# Test2.net
KiCad netlist of a schematic drawn in EAGLE
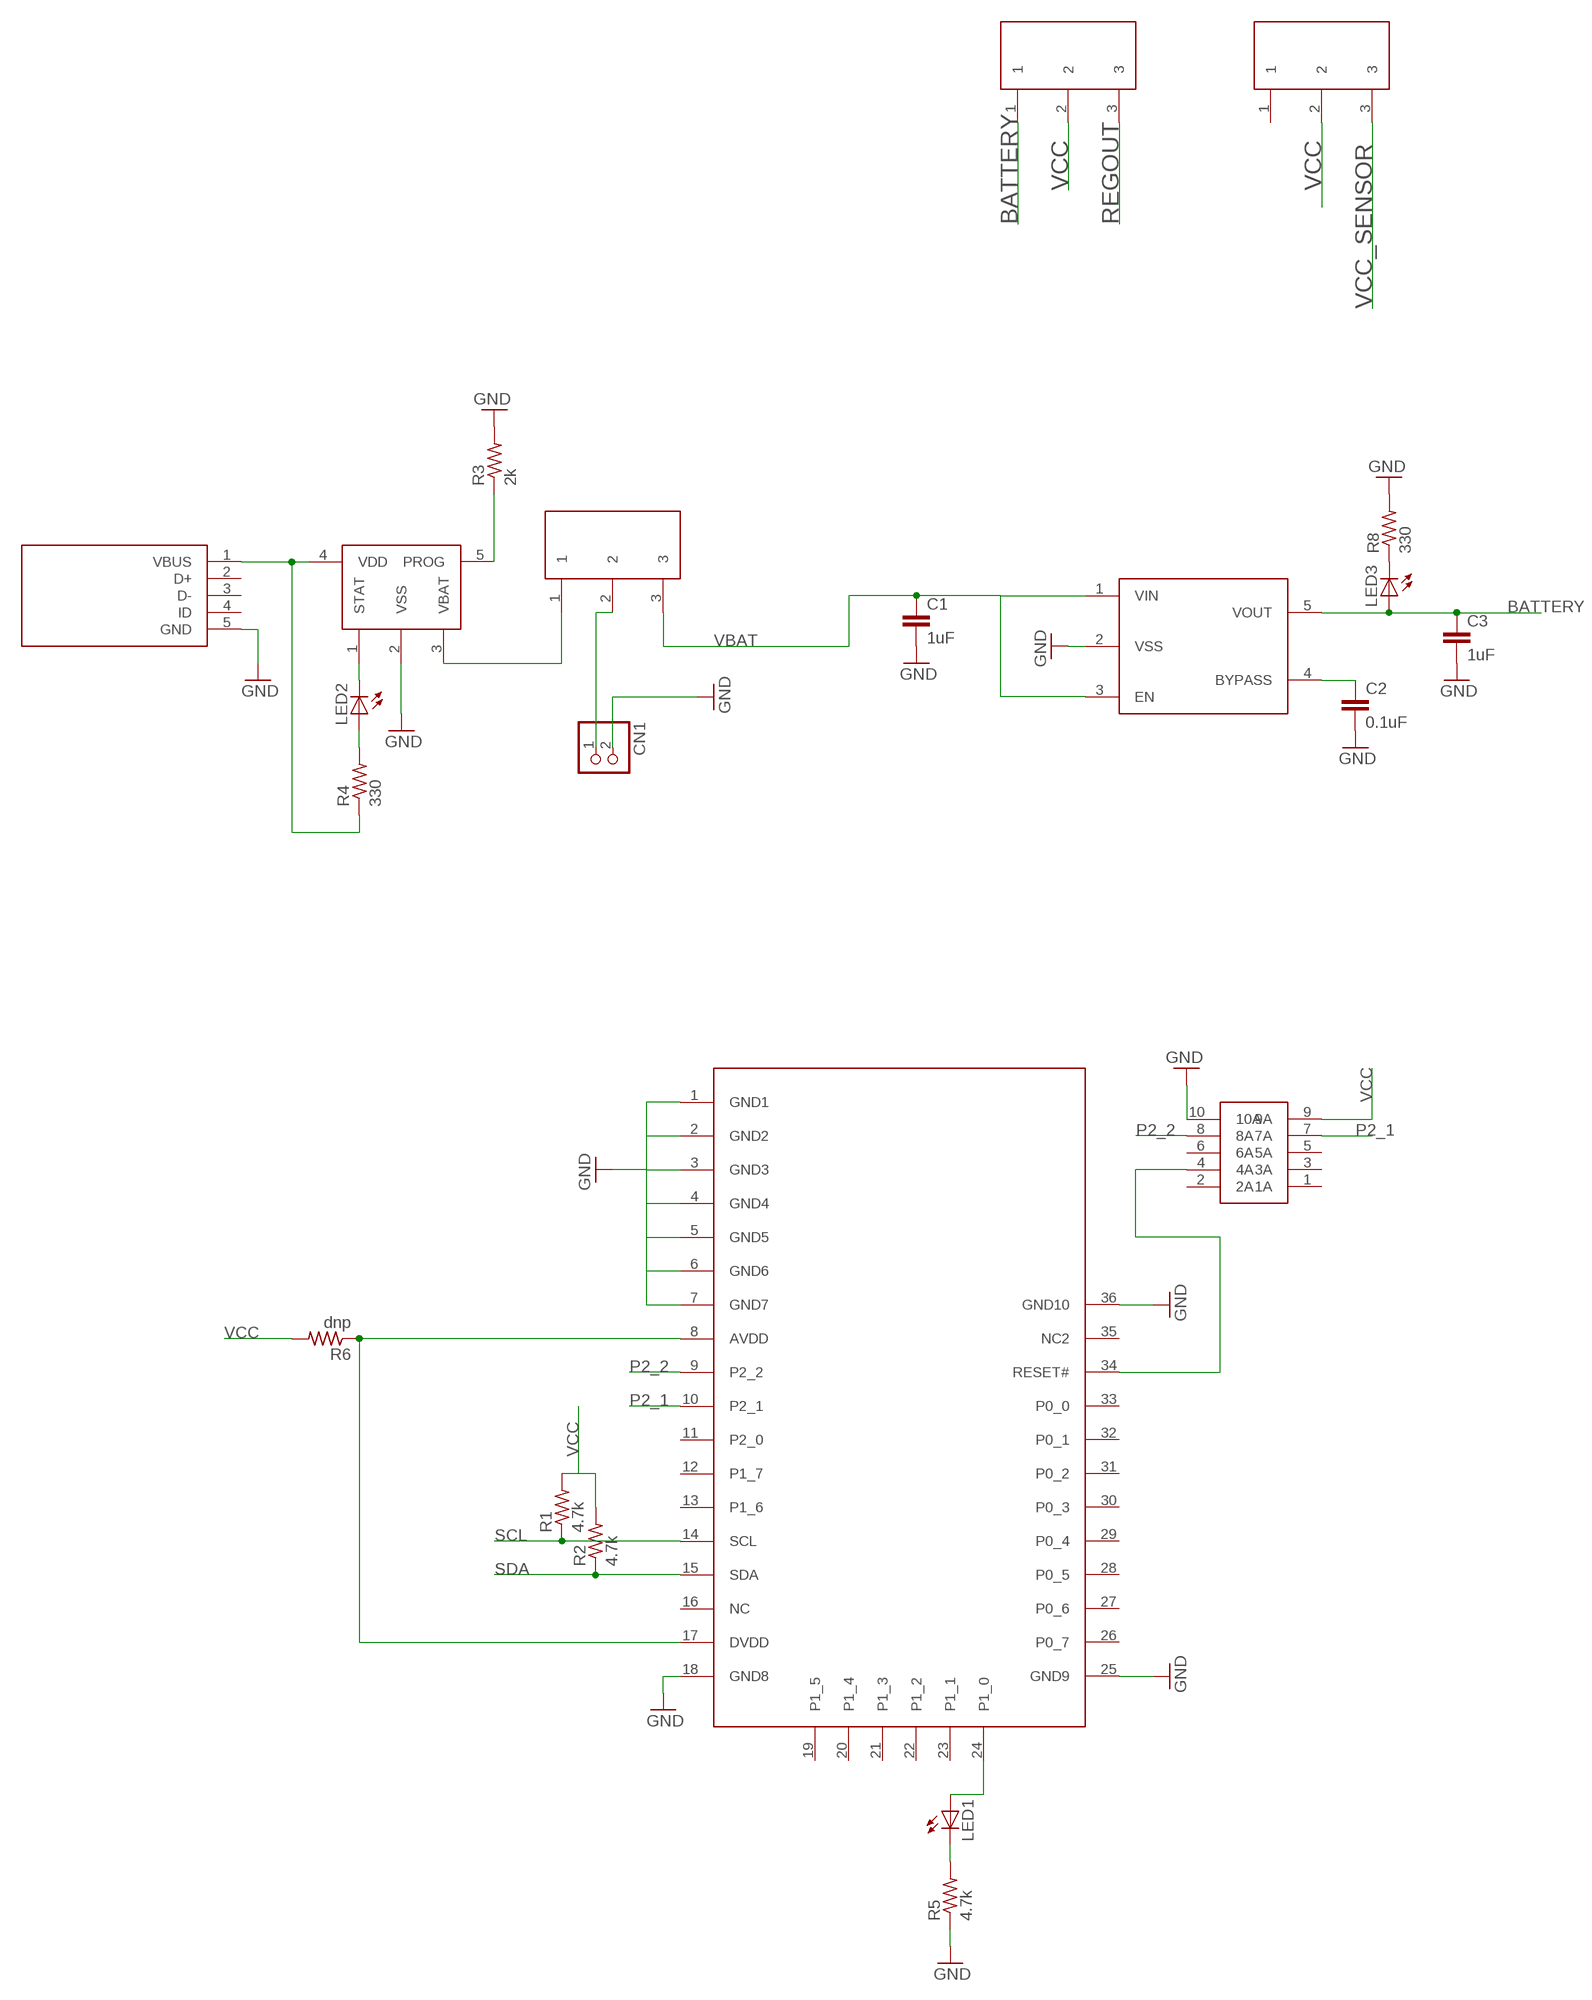
[diagram p0: schematic, sheet 1, part 1 of 2]
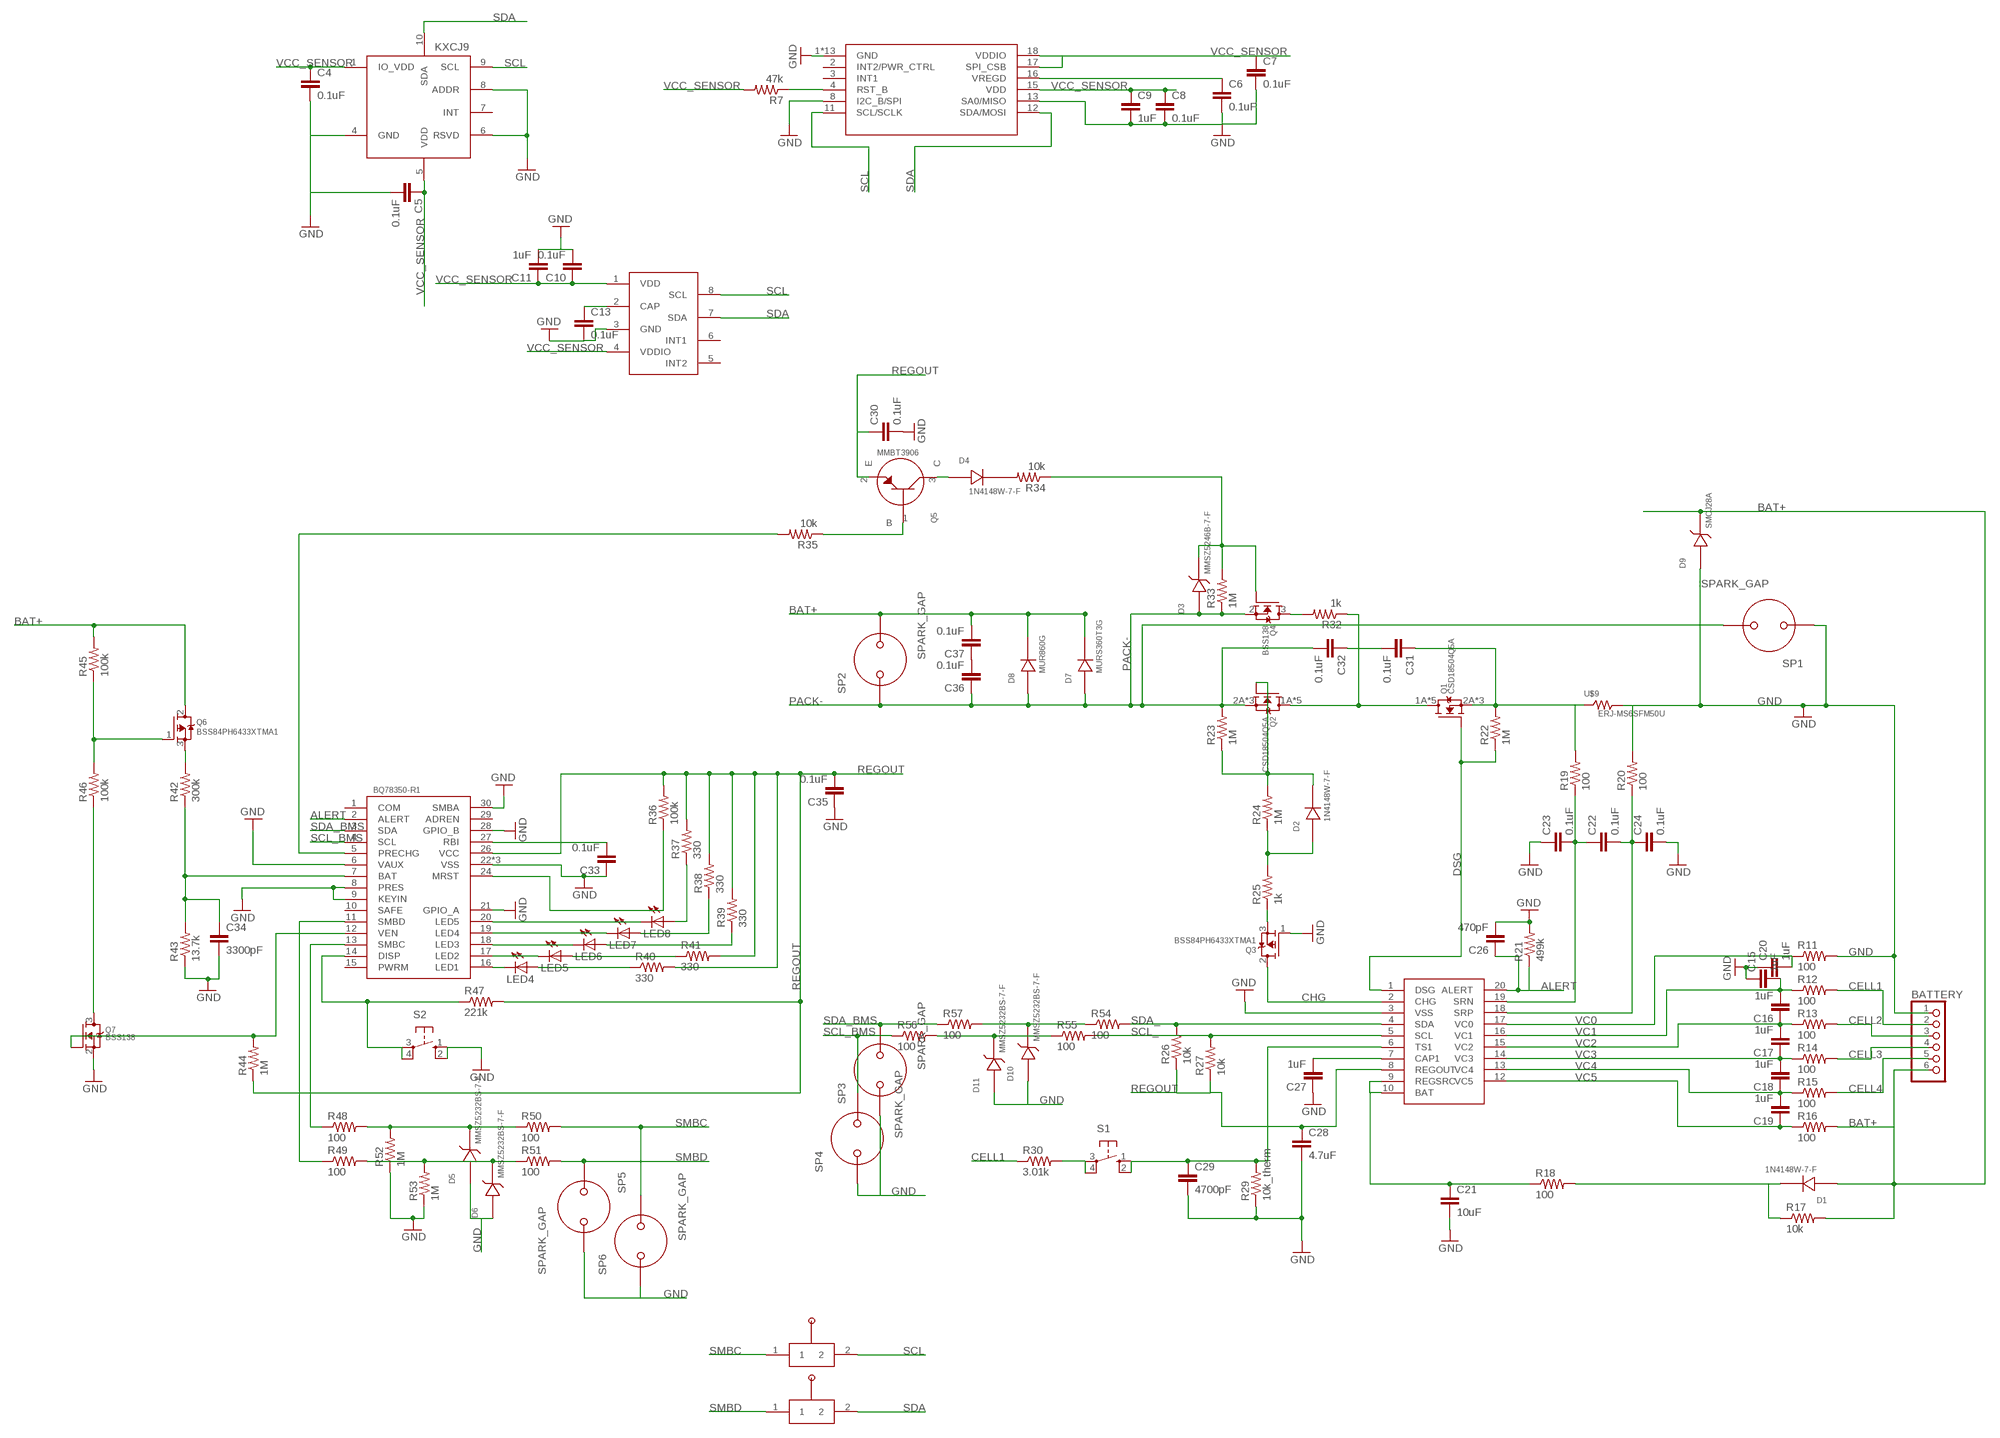
[diagram p1: schematic, sheet 1, part 2 of 2]

(export (version "E")
  (design (tool "Eeschema 10.0.6"))
  (components
    (comp (ref "BATTERY")
      (value "PINHD-1X6")
      (footprint "eagle-import:1X06")
      (libsource (lib "eagle-import") (part "PINHD-1X6"))
    )
    (comp (ref "C1")
      (value "1uF")
      (footprint "eagle-import:C0402")
      (libsource (lib "eagle-import") (part "C-EUC0402"))
    )
    (comp (ref "C2")
      (value "0.1uF")
      (footprint "eagle-import:C0402")
      (libsource (lib "eagle-import") (part "C-EUC0402"))
    )
    (comp (ref "C3")
      (value "1uF")
      (footprint "eagle-import:C0402")
      (libsource (lib "eagle-import") (part "C-EUC0402"))
    )
    (comp (ref "C4")
      (value "0.1uF")
      (footprint "eagle-import:C0402")
      (libsource (lib "eagle-import") (part "C-EUC0402"))
    )
    (comp (ref "C5")
      (value "0.1uF")
      (footprint "eagle-import:C0402")
      (libsource (lib "eagle-import") (part "C-EUC0402"))
    )
    (comp (ref "C6")
      (value "0.1uF")
      (footprint "eagle-import:C0402")
      (libsource (lib "eagle-import") (part "C-EUC0402"))
    )
    (comp (ref "C7")
      (value "0.1uF")
      (footprint "eagle-import:C0402")
      (libsource (lib "eagle-import") (part "C-EUC0402"))
    )
    (comp (ref "C8")
      (value "0.1uF")
      (footprint "eagle-import:C0402")
      (libsource (lib "eagle-import") (part "C-EUC0402"))
    )
    (comp (ref "C9")
      (value "1uF")
      (footprint "eagle-import:C0402")
      (libsource (lib "eagle-import") (part "C-EUC0402"))
    )
    (comp (ref "C10")
      (value "0.1uF")
      (footprint "eagle-import:C0402")
      (libsource (lib "eagle-import") (part "C-EUC0402"))
    )
    (comp (ref "C11")
      (value "1uF")
      (footprint "eagle-import:C0402")
      (libsource (lib "eagle-import") (part "C-EUC0402"))
    )
    (comp (ref "C13")
      (value "0.1uF")
      (footprint "eagle-import:C0402")
      (libsource (lib "eagle-import") (part "C-EUC0402"))
    )
    (comp (ref "C15")
      (value "1uF")
      (footprint "eagle-import:C0805")
      (libsource (lib "eagle-import") (part "C-EUC0805"))
    )
    (comp (ref "C16")
      (value "1uF")
      (footprint "eagle-import:C0805")
      (libsource (lib "eagle-import") (part "C-EUC0805"))
    )
    (comp (ref "C17")
      (value "1uF")
      (footprint "eagle-import:C0805")
      (libsource (lib "eagle-import") (part "C-EUC0805"))
    )
    (comp (ref "C18")
      (value "1uF")
      (footprint "eagle-import:C0805")
      (libsource (lib "eagle-import") (part "C-EUC0805"))
    )
    (comp (ref "C19")
      (value "1uF")
      (footprint "eagle-import:C0805")
      (libsource (lib "eagle-import") (part "C-EUC0805"))
    )
    (comp (ref "C20")
      (value "1uF")
      (footprint "eagle-import:C0805")
      (libsource (lib "eagle-import") (part "C-EUC0805"))
    )
    (comp (ref "C21")
      (value "10uF")
      (footprint "eagle-import:C1206")
      (libsource (lib "eagle-import") (part "C-EUC1206"))
    )
    (comp (ref "C22")
      (value "0.1uF")
      (footprint "eagle-import:C0805")
      (libsource (lib "eagle-import") (part "C-EUC0805"))
    )
    (comp (ref "C23")
      (value "0.1uF")
      (footprint "eagle-import:C0805")
      (libsource (lib "eagle-import") (part "C-EUC0805"))
    )
    (comp (ref "C24")
      (value "0.1uF")
      (footprint "eagle-import:C0805")
      (libsource (lib "eagle-import") (part "C-EUC0805"))
    )
    (comp (ref "C26")
      (value "470pF")
      (footprint "eagle-import:C0805")
      (libsource (lib "eagle-import") (part "C-EUC0805"))
    )
    (comp (ref "C27")
      (value "1uF")
      (footprint "eagle-import:C0805")
      (libsource (lib "eagle-import") (part "C-EUC0805"))
    )
    (comp (ref "C28")
      (value "4.7uF")
      (footprint "eagle-import:C0805")
      (libsource (lib "eagle-import") (part "C-EUC0805"))
    )
    (comp (ref "C29")
      (value "4700pF")
      (footprint "eagle-import:C0402")
      (libsource (lib "eagle-import") (part "C-EUC0402"))
    )
    (comp (ref "C30")
      (value "0.1uF")
      (footprint "eagle-import:C0805")
      (libsource (lib "eagle-import") (part "C-EUC0805"))
    )
    (comp (ref "C31")
      (value "0.1uF")
      (footprint "eagle-import:C0805")
      (libsource (lib "eagle-import") (part "C-EUC0805"))
    )
    (comp (ref "C32")
      (value "0.1uF")
      (footprint "eagle-import:C0805")
      (libsource (lib "eagle-import") (part "C-EUC0805"))
    )
    (comp (ref "C33")
      (value "0.1uF")
      (footprint "eagle-import:C0805")
      (libsource (lib "eagle-import") (part "C-EUC0805"))
    )
    (comp (ref "C34")
      (value "3300pF")
      (footprint "eagle-import:C0402")
      (libsource (lib "eagle-import") (part "C-EUC0402"))
    )
    (comp (ref "C35")
      (value "0.1uF")
      (footprint "eagle-import:C0805")
      (libsource (lib "eagle-import") (part "C-EUC0805"))
    )
    (comp (ref "C36")
      (value "0.1uF")
      (footprint "eagle-import:C0805")
      (libsource (lib "eagle-import") (part "C-EUC0805"))
    )
    (comp (ref "C37")
      (value "0.1uF")
      (footprint "eagle-import:C0805")
      (libsource (lib "eagle-import") (part "C-EUC0805"))
    )
    (comp (ref "CN1")
      (value "JST_2PIN-SMT-RA")
      (footprint "eagle-import:JST-PH-2-SMT-RA")
      (libsource (lib "eagle-import") (part "JST_2PIN-SMT-RA"))
    )
    (comp (ref "D1")
      (value "1N4148W-7-F")
      (footprint "eagle-import:SOD-123")
      (libsource (lib "eagle-import") (part "1N4148W-7-F"))
    )
    (comp (ref "D2")
      (value "1N4148W-7-F")
      (footprint "eagle-import:SOD-123")
      (libsource (lib "eagle-import") (part "1N4148W-7-F"))
    )
    (comp (ref "D3")
      (value "MMSZ5246B-7-F")
      (footprint "eagle-import:SOD-123")
      (libsource (lib "eagle-import") (part "MMSZ5246B-7-F"))
    )
    (comp (ref "D4")
      (value "1N4148W-7-F")
      (footprint "eagle-import:SOD-123")
      (libsource (lib "eagle-import") (part "1N4148W-7-F"))
    )
    (comp (ref "D5")
      (value "MMSZ5232BS-7-F")
      (footprint "eagle-import:SOD-323F")
      (libsource (lib "eagle-import") (part "MMSZ5232BS-7-F"))
    )
    (comp (ref "D6")
      (value "MMSZ5232BS-7-F")
      (footprint "eagle-import:SOD-323F")
      (libsource (lib "eagle-import") (part "MMSZ5232BS-7-F"))
    )
    (comp (ref "D7")
      (value "MURS360T3G")
      (footprint "eagle-import:SMC(DO-214AB)")
      (libsource (lib "eagle-import") (part "MURS360T3G"))
    )
    (comp (ref "D8")
      (value "MUR860G")
      (footprint "eagle-import:TO-220(2RA)")
      (libsource (lib "eagle-import") (part "MUR860G"))
    )
    (comp (ref "D9")
      (value "SMCJ28A")
      (footprint "eagle-import:SMC(DO-214AB)")
      (libsource (lib "eagle-import") (part "SMCJ28A"))
    )
    (comp (ref "D10")
      (value "MMSZ5232BS-7-F")
      (footprint "eagle-import:SOD-323F")
      (libsource (lib "eagle-import") (part "MMSZ5232BS-7-F"))
    )
    (comp (ref "D11")
      (value "MMSZ5232BS-7-F")
      (footprint "eagle-import:SOD-323F")
      (libsource (lib "eagle-import") (part "MMSZ5232BS-7-F"))
    )
    (comp (ref "LED1")
      (value "LEDCHIP-LED0805")
      (footprint "eagle-import:CHIP-LED0805")
      (libsource (lib "eagle-import") (part "LEDCHIP-LED0805"))
    )
    (comp (ref "LED2")
      (value "LEDCHIP-LED0805")
      (footprint "eagle-import:CHIP-LED0805")
      (libsource (lib "eagle-import") (part "LEDCHIP-LED0805"))
    )
    (comp (ref "LED3")
      (value "LEDCHIP-LED0805")
      (footprint "eagle-import:CHIP-LED0805")
      (libsource (lib "eagle-import") (part "LEDCHIP-LED0805"))
    )
    (comp (ref "LED4")
      (value "LEDCHIPLED_0805")
      (footprint "eagle-import:CHIPLED_0805")
      (libsource (lib "eagle-import") (part "LEDCHIPLED_0805"))
    )
    (comp (ref "LED5")
      (value "LEDCHIPLED_0805")
      (footprint "eagle-import:CHIPLED_0805")
      (libsource (lib "eagle-import") (part "LEDCHIPLED_0805"))
    )
    (comp (ref "LED6")
      (value "LEDCHIPLED_0805")
      (footprint "eagle-import:CHIPLED_0805")
      (libsource (lib "eagle-import") (part "LEDCHIPLED_0805"))
    )
    (comp (ref "LED7")
      (value "LEDCHIPLED_0805")
      (footprint "eagle-import:CHIPLED_0805")
      (libsource (lib "eagle-import") (part "LEDCHIPLED_0805"))
    )
    (comp (ref "LED8")
      (value "LEDCHIPLED_0805")
      (footprint "eagle-import:CHIPLED_0805")
      (libsource (lib "eagle-import") (part "LEDCHIPLED_0805"))
    )
    (comp (ref "Q1")
      (value "CSD18504Q5A")
      (footprint "eagle-import:Q5A")
      (libsource (lib "eagle-import") (part "CSD18504Q5A"))
    )
    (comp (ref "Q2")
      (value "CSD18504Q5A")
      (footprint "eagle-import:Q5A")
      (libsource (lib "eagle-import") (part "CSD18504Q5A"))
    )
    (comp (ref "Q3")
      (value "BSS84PH6433XTMA1")
      (footprint "eagle-import:SOT23-3")
      (libsource (lib "eagle-import") (part "BSS84PH6433XTMA1"))
    )
    (comp (ref "Q4")
      (value "BSS138")
      (footprint "eagle-import:SOT23-3")
      (libsource (lib "eagle-import") (part "BSS138"))
    )
    (comp (ref "Q5")
      (value "MMBT3906")
      (footprint "eagle-import:SOT23-3")
      (libsource (lib "eagle-import") (part "MMBT3906"))
    )
    (comp (ref "Q6")
      (value "BSS84PH6433XTMA1")
      (footprint "eagle-import:SOT23-3")
      (libsource (lib "eagle-import") (part "BSS84PH6433XTMA1"))
    )
    (comp (ref "Q7")
      (value "BSS138")
      (footprint "eagle-import:SOT23-3")
      (libsource (lib "eagle-import") (part "BSS138"))
    )
    (comp (ref "R1")
      (value "4.7k")
      (footprint "eagle-import:R0402")
      (libsource (lib "eagle-import") (part "R-US_R0402"))
    )
    (comp (ref "R2")
      (value "4.7k")
      (footprint "eagle-import:R0402")
      (libsource (lib "eagle-import") (part "R-US_R0402"))
    )
    (comp (ref "R3")
      (value "2k")
      (footprint "eagle-import:R0402")
      (libsource (lib "eagle-import") (part "R-US_R0402"))
    )
    (comp (ref "R4")
      (value "330")
      (footprint "eagle-import:R0402")
      (libsource (lib "eagle-import") (part "R-US_R0402"))
    )
    (comp (ref "R5")
      (value "4.7k")
      (footprint "eagle-import:R0402")
      (libsource (lib "eagle-import") (part "R-US_R0402"))
    )
    (comp (ref "R6")
      (value "dnp")
      (footprint "eagle-import:R0402")
      (libsource (lib "eagle-import") (part "R-US_R0402"))
    )
    (comp (ref "R7")
      (value "47k")
      (footprint "eagle-import:R0402")
      (libsource (lib "eagle-import") (part "R-US_R0402"))
    )
    (comp (ref "R8")
      (value "330")
      (footprint "eagle-import:R0402")
      (libsource (lib "eagle-import") (part "R-US_R0402"))
    )
    (comp (ref "R11")
      (value "100")
      (footprint "eagle-import:R1206")
      (libsource (lib "eagle-import") (part "R-US_R1206"))
    )
    (comp (ref "R12")
      (value "100")
      (footprint "eagle-import:R1206")
      (libsource (lib "eagle-import") (part "R-US_R1206"))
    )
    (comp (ref "R13")
      (value "100")
      (footprint "eagle-import:R1206")
      (libsource (lib "eagle-import") (part "R-US_R1206"))
    )
    (comp (ref "R14")
      (value "100")
      (footprint "eagle-import:R1206")
      (libsource (lib "eagle-import") (part "R-US_R1206"))
    )
    (comp (ref "R15")
      (value "100")
      (footprint "eagle-import:R1206")
      (libsource (lib "eagle-import") (part "R-US_R1206"))
    )
    (comp (ref "R16")
      (value "100")
      (footprint "eagle-import:R1206")
      (libsource (lib "eagle-import") (part "R-US_R1206"))
    )
    (comp (ref "R17")
      (value "10k")
      (footprint "eagle-import:R0805")
      (libsource (lib "eagle-import") (part "R-US_R0805"))
    )
    (comp (ref "R18")
      (value "100")
      (footprint "eagle-import:R0805")
      (libsource (lib "eagle-import") (part "R-US_R0805"))
    )
    (comp (ref "R19")
      (value "100")
      (footprint "eagle-import:R0805")
      (libsource (lib "eagle-import") (part "R-US_R0805"))
    )
    (comp (ref "R20")
      (value "100")
      (footprint "eagle-import:R0805")
      (libsource (lib "eagle-import") (part "R-US_R0805"))
    )
    (comp (ref "R21")
      (value "499k")
      (footprint "eagle-import:R0805")
      (libsource (lib "eagle-import") (part "R-US_R0805"))
    )
    (comp (ref "R22")
      (value "1M")
      (footprint "eagle-import:R1206")
      (libsource (lib "eagle-import") (part "R-US_R1206"))
    )
    (comp (ref "R23")
      (value "1M")
      (footprint "eagle-import:R1206")
      (libsource (lib "eagle-import") (part "R-US_R1206"))
    )
    (comp (ref "R24")
      (value "1M")
      (footprint "eagle-import:R1206")
      (libsource (lib "eagle-import") (part "R-US_R1206"))
    )
    (comp (ref "R25")
      (value "1k")
      (footprint "eagle-import:R0805")
      (libsource (lib "eagle-import") (part "R-US_R0805"))
    )
    (comp (ref "R26")
      (value "10k")
      (footprint "eagle-import:R0805")
      (libsource (lib "eagle-import") (part "R-US_R0805"))
    )
    (comp (ref "R27")
      (value "10k")
      (footprint "eagle-import:R0805")
      (libsource (lib "eagle-import") (part "R-US_R0805"))
    )
    (comp (ref "R29")
      (value "10k_therm")
      (footprint "eagle-import:R0402")
      (libsource (lib "eagle-import") (part "R-US_R0402"))
    )
    (comp (ref "R30")
      (value "3.01k")
      (footprint "eagle-import:R0805")
      (libsource (lib "eagle-import") (part "R-US_R0805"))
    )
    (comp (ref "R32")
      (value "1k")
      (footprint "eagle-import:R2512")
      (libsource (lib "eagle-import") (part "R-US_R2512"))
    )
    (comp (ref "R33")
      (value "1M")
      (footprint "eagle-import:R1206")
      (libsource (lib "eagle-import") (part "R-US_R1206"))
    )
    (comp (ref "R34")
      (value "10k")
      (footprint "eagle-import:R0805")
      (libsource (lib "eagle-import") (part "R-US_R0805"))
    )
    (comp (ref "R35")
      (value "10k")
      (footprint "eagle-import:R0805")
      (libsource (lib "eagle-import") (part "R-US_R0805"))
    )
    (comp (ref "R36")
      (value "100k")
      (footprint "eagle-import:R0805")
      (libsource (lib "eagle-import") (part "R-US_R0805"))
    )
    (comp (ref "R37")
      (value "330")
      (footprint "eagle-import:R0402")
      (libsource (lib "eagle-import") (part "R-US_R0402"))
    )
    (comp (ref "R38")
      (value "330")
      (footprint "eagle-import:R0402")
      (libsource (lib "eagle-import") (part "R-US_R0402"))
    )
    (comp (ref "R39")
      (value "330")
      (footprint "eagle-import:R0402")
      (libsource (lib "eagle-import") (part "R-US_R0402"))
    )
    (comp (ref "R40")
      (value "330")
      (footprint "eagle-import:R0402")
      (libsource (lib "eagle-import") (part "R-US_R0402"))
    )
    (comp (ref "R41")
      (value "330")
      (footprint "eagle-import:R0402")
      (libsource (lib "eagle-import") (part "R-US_R0402"))
    )
    (comp (ref "R42")
      (value "300k")
      (footprint "eagle-import:R0805")
      (libsource (lib "eagle-import") (part "R-US_R0805"))
    )
    (comp (ref "R43")
      (value "13.7k")
      (footprint "eagle-import:R0805")
      (libsource (lib "eagle-import") (part "R-US_R0805"))
    )
    (comp (ref "R44")
      (value "1M")
      (footprint "eagle-import:R1206")
      (libsource (lib "eagle-import") (part "R-US_R1206"))
    )
    (comp (ref "R45")
      (value "100k")
      (footprint "eagle-import:R0805")
      (libsource (lib "eagle-import") (part "R-US_R0805"))
    )
    (comp (ref "R46")
      (value "100k")
      (footprint "eagle-import:R0805")
      (libsource (lib "eagle-import") (part "R-US_R0805"))
    )
    (comp (ref "R47")
      (value "221k")
      (footprint "eagle-import:R0805")
      (libsource (lib "eagle-import") (part "R-US_R0805"))
    )
    (comp (ref "R48")
      (value "100")
      (footprint "eagle-import:R0805")
      (libsource (lib "eagle-import") (part "R-US_R0805"))
    )
    (comp (ref "R49")
      (value "100")
      (footprint "eagle-import:R0805")
      (libsource (lib "eagle-import") (part "R-US_R0805"))
    )
    (comp (ref "R50")
      (value "100")
      (footprint "eagle-import:R0805")
      (libsource (lib "eagle-import") (part "R-US_R0805"))
    )
    (comp (ref "R51")
      (value "100")
      (footprint "eagle-import:R0805")
      (libsource (lib "eagle-import") (part "R-US_R0805"))
    )
    (comp (ref "R52")
      (value "1M")
      (footprint "eagle-import:R1206")
      (libsource (lib "eagle-import") (part "R-US_R1206"))
    )
    (comp (ref "R53")
      (value "1M")
      (footprint "eagle-import:R1206")
      (libsource (lib "eagle-import") (part "R-US_R1206"))
    )
    (comp (ref "R54")
      (value "100")
      (footprint "eagle-import:R0805")
      (libsource (lib "eagle-import") (part "R-US_R0805"))
    )
    (comp (ref "R55")
      (value "100")
      (footprint "eagle-import:R0805")
      (libsource (lib "eagle-import") (part "R-US_R0805"))
    )
    (comp (ref "R56")
      (value "100")
      (footprint "eagle-import:R0805")
      (libsource (lib "eagle-import") (part "R-US_R0805"))
    )
    (comp (ref "R57")
      (value "100")
      (footprint "eagle-import:R0805")
      (libsource (lib "eagle-import") (part "R-US_R0805"))
    )
    (comp (ref "S1")
      (value "10-XX")
      (footprint "eagle-import:B3F-10XX")
      (fields (field (name "MPN") "B3F-1000"))
      (libsource (lib "eagle-import") (part "10-XX"))
    )
    (comp (ref "S2")
      (value "10-XX")
      (footprint "eagle-import:B3F-10XX")
      (fields (field (name "MPN") "B3F-1000"))
      (libsource (lib "eagle-import") (part "10-XX"))
    )
    (comp (ref "SP1")
      (value "SPARK_GAP")
      (footprint "eagle-import:SPARK_GAP")
      (libsource (lib "eagle-import") (part "SPARK_GAP"))
    )
    (comp (ref "SP2")
      (value "SPARK_GAP")
      (footprint "eagle-import:SPARK_GAP")
      (libsource (lib "eagle-import") (part "SPARK_GAP"))
    )
    (comp (ref "SP3")
      (value "SPARK_GAP")
      (footprint "eagle-import:SPARK_GAP")
      (libsource (lib "eagle-import") (part "SPARK_GAP"))
    )
    (comp (ref "SP4")
      (value "SPARK_GAP")
      (footprint "eagle-import:SPARK_GAP")
      (libsource (lib "eagle-import") (part "SPARK_GAP"))
    )
    (comp (ref "SP5")
      (value "SPARK_GAP")
      (footprint "eagle-import:SPARK_GAP")
      (libsource (lib "eagle-import") (part "SPARK_GAP"))
    )
    (comp (ref "SP6")
      (value "SPARK_GAP")
      (footprint "eagle-import:SPARK_GAP")
      (libsource (lib "eagle-import") (part "SPARK_GAP"))
    )
    (comp (ref "U$1")
      (value "BQ76920")
      (footprint "eagle-import:SOIC-20")
      (libsource (lib "eagle-import") (part "BQ76920"))
    )
    (comp (ref "U$2")
      (value "BLE113")
      (footprint "eagle-import:BLUEGIGA")
      (libsource (lib "eagle-import") (part "BLE113"))
    )
    (comp (ref "U$3")
      (value "RIBBON_10POS_MALE")
      (footprint "eagle-import:RIBBON_10POS_MALE")
      (libsource (lib "eagle-import") (part "RIBBON_10POS_MALE"))
    )
    (comp (ref "U$4")
      (value "LP3985")
      (footprint "eagle-import:SOT23-5L")
      (libsource (lib "eagle-import") (part "LP3985"))
    )
    (comp (ref "U$5")
      (value "SPDT_THRU")
      (footprint "eagle-import:SPDT_THRU")
      (libsource (lib "eagle-import") (part "SPDT_THRU"))
    )
    (comp (ref "U$6")
      (value "USB_MINI")
      (footprint "eagle-import:USB_MINI")
      (libsource (lib "eagle-import") (part "USB_MINI"))
    )
    (comp (ref "U$7")
      (value "KXCJ9")
      (footprint "eagle-import:KXCJ9")
      (libsource (lib "eagle-import") (part "KXCJ9"))
    )
    (comp (ref "U$8")
      (value "FXAS21002")
      (footprint "eagle-import:FXAS21002")
      (libsource (lib "eagle-import") (part "FXAS21002"))
    )
    (comp (ref "U$9")
      (value "ERJ-MS6SFM50U")
      (footprint "eagle-import:ERJ-MS6SFM50U")
      (libsource (lib "eagle-import") (part "ERJ-MS6SFM50U"))
    )
    (comp (ref "U$10")
      (value "BQ78350-R1")
      (footprint "eagle-import:SOIC-30")
      (libsource (lib "eagle-import") (part "BQ78350-R1"))
    )
    (comp (ref "U$11")
      (value "SPDT_THRU")
      (footprint "eagle-import:SPDT_THRU")
      (libsource (lib "eagle-import") (part "SPDT_THRU"))
    )
    (comp (ref "U$12")
      (value "SPDT_THRU")
      (footprint "eagle-import:SPDT_THRU")
      (libsource (lib "eagle-import") (part "SPDT_THRU"))
    )
    (comp (ref "U$13")
      (value "MCP73831")
      (footprint "eagle-import:MCP73831")
      (libsource (lib "eagle-import") (part "MCP73831"))
    )
    (comp (ref "U$14")
      (value "MLP3115A2")
      (footprint "eagle-import:MLP3115A2")
      (libsource (lib "eagle-import") (part "MLP3115A2"))
    )
    (comp (ref "U$16")
      (value "MANUAL_SWITCH")
      (footprint "eagle-import:MANUAL_SWITCH")
      (libsource (lib "eagle-import") (part "MANUAL_SWITCH"))
    )
    (comp (ref "U$17")
      (value "MANUAL_SWITCH")
      (footprint "eagle-import:MANUAL_SWITCH")
      (libsource (lib "eagle-import") (part "MANUAL_SWITCH"))
    )
  )
  (nets
    (net (code "1") (name "/ALERT") (class "Default")
      (node (ref "C26") (pin "1") (pinfunction "1_1") (pintype "passive"))
      (node (ref "R21") (pin "1") (pinfunction "1_1") (pintype "passive"))
      (node (ref "U$1") (pin "20") (pinfunction "ALERT_20") (pintype "bidirectional"))
      (node (ref "U$10") (pin "2") (pinfunction "ALERT_2") (pintype "bidirectional"))
    )
    (net (code "2") (name "/BAT+") (class "Default")
      (node (ref "BATTERY") (pin "6") (pinfunction "6_6") (pintype "passive"))
      (node (ref "C37") (pin "2") (pinfunction "2_2") (pintype "passive"))
      (node (ref "D1") (pin "P$1") (pinfunction "P$1_P$1") (pintype "bidirectional"))
      (node (ref "D7") (pin "2") (pinfunction "P$2_2") (pintype "bidirectional"))
      (node (ref "D8") (pin "P$3") (pinfunction "P$2_P$3") (pintype "bidirectional"))
      (node (ref "D9") (pin "2") (pinfunction "2_2") (pintype "bidirectional"))
      (node (ref "Q6") (pin "2") (pinfunction "S_2") (pintype "bidirectional"))
      (node (ref "R16") (pin "2") (pinfunction "2_2") (pintype "passive"))
      (node (ref "R17") (pin "2") (pinfunction "2_2") (pintype "passive"))
      (node (ref "R45") (pin "2") (pinfunction "2_2") (pintype "passive"))
      (node (ref "SP2") (pin "P$2") (pinfunction "P$2_P$2") (pintype "bidirectional"))
    )
    (net (code "3") (name "/BATTERY") (class "Default")
      (node (ref "C3") (pin "1") (pinfunction "1_1") (pintype "passive"))
      (node (ref "LED3") (pin "A") (pinfunction "A_A") (pintype "passive"))
      (node (ref "U$11") (pin "1") (pinfunction "1_1") (pintype "bidirectional"))
      (node (ref "U$4") (pin "5") (pinfunction "VOUT_5") (pintype "bidirectional"))
    )
    (net (code "4") (name "/CELL1") (class "Default")
      (node (ref "BATTERY") (pin "2") (pinfunction "2_2") (pintype "passive"))
      (node (ref "R12") (pin "2") (pinfunction "2_2") (pintype "passive"))
      (node (ref "R30") (pin "1") (pinfunction "1_1") (pintype "passive"))
    )
    (net (code "5") (name "/CELL2") (class "Default")
      (node (ref "BATTERY") (pin "3") (pinfunction "3_3") (pintype "passive"))
      (node (ref "R13") (pin "2") (pinfunction "2_2") (pintype "passive"))
    )
    (net (code "6") (name "/CELL3") (class "Default")
      (node (ref "BATTERY") (pin "4") (pinfunction "4_4") (pintype "passive"))
      (node (ref "R14") (pin "2") (pinfunction "2_2") (pintype "passive"))
    )
    (net (code "7") (name "/CELL4") (class "Default")
      (node (ref "BATTERY") (pin "5") (pinfunction "5_5") (pintype "passive"))
      (node (ref "R15") (pin "2") (pinfunction "2_2") (pintype "passive"))
    )
    (net (code "8") (name "/CHG") (class "Default")
      (node (ref "Q3") (pin "2") (pinfunction "S_2") (pintype "bidirectional"))
      (node (ref "U$1") (pin "2") (pinfunction "CHG_2") (pintype "bidirectional"))
    )
    (net (code "9") (name "/DSG") (class "Default")
      (node (ref "Q1") (pin "3A") (pinfunction "G_3A") (pintype "bidirectional"))
      (node (ref "R22") (pin "1") (pinfunction "1_1") (pintype "passive"))
      (node (ref "U$1") (pin "1") (pinfunction "DSG_1") (pintype "bidirectional"))
    )
    (net (code "10") (name "/P2_1") (class "Default")
      (node (ref "U$2") (pin "10") (pinfunction "P2_1_10") (pintype "bidirectional"))
      (node (ref "U$3") (pin "7") (pinfunction "7A_7") (pintype "bidirectional"))
    )
    (net (code "11") (name "/P2_2") (class "Default")
      (node (ref "U$2") (pin "9") (pinfunction "P2_2_9") (pintype "bidirectional"))
      (node (ref "U$3") (pin "8") (pinfunction "8A_8") (pintype "bidirectional"))
    )
    (net (code "12") (name "/PACK-") (class "Default")
      (node (ref "C32") (pin "2") (pinfunction "2_2") (pintype "passive"))
      (node (ref "C36") (pin "1") (pinfunction "1_1") (pintype "passive"))
      (node (ref "D3") (pin "P$1") (pinfunction "1_P$1") (pintype "bidirectional"))
      (node (ref "D7") (pin "1") (pinfunction "P$1_1") (pintype "bidirectional"))
      (node (ref "D8") (pin "P$1") (pinfunction "P$1_P$1") (pintype "bidirectional"))
      (node (ref "D8") (pin "P$4") (pinfunction "P$1_P$4") (pintype "bidirectional"))
      (node (ref "Q2") (pin "2A") (pinfunction "S_2A") (pintype "bidirectional"))
      (node (ref "Q2") (pin "2B") (pinfunction "S_2B") (pintype "bidirectional"))
      (node (ref "Q2") (pin "2C") (pinfunction "S_2C") (pintype "bidirectional"))
      (node (ref "Q4") (pin "2") (pinfunction "S_2") (pintype "bidirectional"))
      (node (ref "R23") (pin "2") (pinfunction "2_2") (pintype "passive"))
      (node (ref "R33") (pin "1") (pinfunction "1_1") (pintype "passive"))
      (node (ref "SP1") (pin "P$2") (pinfunction "P$2_P$2") (pintype "bidirectional"))
      (node (ref "SP2") (pin "P$1") (pinfunction "P$1_P$1") (pintype "bidirectional"))
    )
    (net (code "13") (name "/REGOUT") (class "Default")
      (node (ref "C28") (pin "1") (pinfunction "1_1") (pintype "passive"))
      (node (ref "C30") (pin "1") (pinfunction "1_1") (pintype "passive"))
      (node (ref "C35") (pin "2") (pinfunction "2_2") (pintype "passive"))
      (node (ref "Q5") (pin "2") (pinfunction "E_2") (pintype "bidirectional"))
      (node (ref "R26") (pin "1") (pinfunction "1_1") (pintype "passive"))
      (node (ref "R27") (pin "1") (pinfunction "1_1") (pintype "passive"))
      (node (ref "R36") (pin "2") (pinfunction "2_2") (pintype "passive"))
      (node (ref "R37") (pin "2") (pinfunction "2_2") (pintype "passive"))
      (node (ref "R38") (pin "2") (pinfunction "2_2") (pintype "passive"))
      (node (ref "R39") (pin "2") (pinfunction "2_2") (pintype "passive"))
      (node (ref "R40") (pin "2") (pinfunction "2_2") (pintype "passive"))
      (node (ref "R41") (pin "2") (pinfunction "2_2") (pintype "passive"))
      (node (ref "R44") (pin "1") (pinfunction "1_1") (pintype "passive"))
      (node (ref "R47") (pin "2") (pinfunction "2_2") (pintype "passive"))
      (node (ref "U$1") (pin "8") (pinfunction "REGOUT_8") (pintype "bidirectional"))
      (node (ref "U$10") (pin "26") (pinfunction "VCC_26") (pintype "bidirectional"))
      (node (ref "U$11") (pin "3") (pinfunction "3_3") (pintype "bidirectional"))
    )
    (net (code "14") (name "/SCL") (class "Default")
      (node (ref "R1") (pin "1") (pinfunction "1_1") (pintype "passive"))
      (node (ref "U$14") (pin "8") (pinfunction "SCL_8") (pintype "bidirectional"))
      (node (ref "U$16") (pin "2") (pinfunction "2_2") (pintype "bidirectional"))
      (node (ref "U$2") (pin "14") (pinfunction "SCL_14") (pintype "bidirectional"))
      (node (ref "U$7") (pin "9") (pinfunction "SCL_9") (pintype "bidirectional"))
      (node (ref "U$8") (pin "11") (pinfunction "SCL/SCLK_11") (pintype "bidirectional"))
    )
    (net (code "15") (name "/SCL_") (class "Default")
      (node (ref "R27") (pin "2") (pinfunction "2_2") (pintype "passive"))
      (node (ref "R55") (pin "2") (pinfunction "2_2") (pintype "passive"))
      (node (ref "U$1") (pin "5") (pinfunction "SCL_5") (pintype "bidirectional"))
    )
    (net (code "16") (name "/SCL_BMS") (class "Default")
      (node (ref "R56") (pin "1") (pinfunction "1_1") (pintype "passive"))
      (node (ref "SP4") (pin "P$2") (pinfunction "P$2_P$2") (pintype "bidirectional"))
      (node (ref "U$10") (pin "4") (pinfunction "SCL_4") (pintype "bidirectional"))
    )
    (net (code "17") (name "/SDA") (class "Default")
      (node (ref "R2") (pin "1") (pinfunction "1_1") (pintype "passive"))
      (node (ref "U$14") (pin "7") (pinfunction "SDA_7") (pintype "bidirectional"))
      (node (ref "U$17") (pin "2") (pinfunction "2_2") (pintype "bidirectional"))
      (node (ref "U$2") (pin "15") (pinfunction "SDA_15") (pintype "bidirectional"))
      (node (ref "U$7") (pin "10") (pinfunction "SDA_10") (pintype "bidirectional"))
      (node (ref "U$8") (pin "12") (pinfunction "SDA/MOSI_12") (pintype "bidirectional"))
    )
    (net (code "18") (name "/SDA_") (class "Default")
      (node (ref "R26") (pin "2") (pinfunction "2_2") (pintype "passive"))
      (node (ref "R54") (pin "2") (pinfunction "2_2") (pintype "passive"))
      (node (ref "U$1") (pin "4") (pinfunction "SDA_4") (pintype "bidirectional"))
    )
    (net (code "19") (name "/SDA_BMS") (class "Default")
      (node (ref "R57") (pin "1") (pinfunction "1_1") (pintype "passive"))
      (node (ref "SP3") (pin "P$2") (pinfunction "P$2_P$2") (pintype "bidirectional"))
      (node (ref "U$10") (pin "3") (pinfunction "SDA_3") (pintype "bidirectional"))
    )
    (net (code "20") (name "/SMBC") (class "Default")
      (node (ref "R50") (pin "2") (pinfunction "2_2") (pintype "passive"))
      (node (ref "SP6") (pin "P$2") (pinfunction "P$2_P$2") (pintype "bidirectional"))
      (node (ref "U$16") (pin "1") (pinfunction "1_1") (pintype "bidirectional"))
    )
    (net (code "21") (name "/SMBD") (class "Default")
      (node (ref "R51") (pin "2") (pinfunction "2_2") (pintype "passive"))
      (node (ref "SP5") (pin "P$1") (pinfunction "P$1_P$1") (pintype "bidirectional"))
      (node (ref "U$17") (pin "1") (pinfunction "1_1") (pintype "bidirectional"))
    )
    (net (code "22") (name "/VBAT") (class "Default")
      (node (ref "C1") (pin "1") (pinfunction "1_1") (pintype "passive"))
      (node (ref "U$4") (pin "1") (pinfunction "VIN_1") (pintype "bidirectional"))
      (node (ref "U$4") (pin "3") (pinfunction "EN_3") (pintype "bidirectional"))
      (node (ref "U$5") (pin "3") (pinfunction "3_3") (pintype "bidirectional"))
    )
    (net (code "23") (name "/VC0") (class "Default")
      (node (ref "C20") (pin "2") (pinfunction "2_2") (pintype "passive"))
      (node (ref "R11") (pin "1") (pinfunction "1_1") (pintype "passive"))
      (node (ref "U$1") (pin "17") (pinfunction "VC0_17") (pintype "bidirectional"))
    )
    (net (code "24") (name "/VC1") (class "Default")
      (node (ref "C15") (pin "2") (pinfunction "2_2") (pintype "passive"))
      (node (ref "C16") (pin "2") (pinfunction "2_2") (pintype "passive"))
      (node (ref "R12") (pin "1") (pinfunction "1_1") (pintype "passive"))
      (node (ref "U$1") (pin "16") (pinfunction "VC1_16") (pintype "bidirectional"))
    )
    (net (code "25") (name "/VC2") (class "Default")
      (node (ref "C16") (pin "1") (pinfunction "1_1") (pintype "passive"))
      (node (ref "C17") (pin "2") (pinfunction "2_2") (pintype "passive"))
      (node (ref "R13") (pin "1") (pinfunction "1_1") (pintype "passive"))
      (node (ref "U$1") (pin "15") (pinfunction "VC2_15") (pintype "bidirectional"))
    )
    (net (code "26") (name "/VC3") (class "Default")
      (node (ref "C17") (pin "1") (pinfunction "1_1") (pintype "passive"))
      (node (ref "C18") (pin "2") (pinfunction "2_2") (pintype "passive"))
      (node (ref "R14") (pin "1") (pinfunction "1_1") (pintype "passive"))
      (node (ref "U$1") (pin "14") (pinfunction "VC3_14") (pintype "bidirectional"))
    )
    (net (code "27") (name "/VC4") (class "Default")
      (node (ref "C18") (pin "1") (pinfunction "1_1") (pintype "passive"))
      (node (ref "C19") (pin "2") (pinfunction "2_2") (pintype "passive"))
      (node (ref "R15") (pin "1") (pinfunction "1_1") (pintype "passive"))
      (node (ref "U$1") (pin "13") (pinfunction "VC4_13") (pintype "bidirectional"))
    )
    (net (code "28") (name "/VC5") (class "Default")
      (node (ref "C19") (pin "1") (pinfunction "1_1") (pintype "passive"))
      (node (ref "R16") (pin "1") (pinfunction "1_1") (pintype "passive"))
      (node (ref "U$1") (pin "12") (pinfunction "VC5_12") (pintype "bidirectional"))
    )
    (net (code "29") (name "/VCC") (class "Default")
      (node (ref "R1") (pin "2") (pinfunction "2_2") (pintype "passive"))
      (node (ref "R2") (pin "2") (pinfunction "2_2") (pintype "passive"))
      (node (ref "R6") (pin "2") (pinfunction "2_2") (pintype "passive"))
      (node (ref "U$11") (pin "2") (pinfunction "2_2") (pintype "bidirectional"))
      (node (ref "U$12") (pin "2") (pinfunction "2_2") (pintype "bidirectional"))
      (node (ref "U$3") (pin "9") (pinfunction "9A_9") (pintype "bidirectional"))
    )
    (net (code "30") (name "/VCC_SENSOR") (class "Default")
      (node (ref "C10") (pin "1") (pinfunction "1_1") (pintype "passive"))
      (node (ref "C11") (pin "1") (pinfunction "1_1") (pintype "passive"))
      (node (ref "C4") (pin "1") (pinfunction "1_1") (pintype "passive"))
      (node (ref "C5") (pin "1") (pinfunction "1_1") (pintype "passive"))
      (node (ref "C7") (pin "1") (pinfunction "1_1") (pintype "passive"))
      (node (ref "C8") (pin "1") (pinfunction "1_1") (pintype "passive"))
      (node (ref "C9") (pin "1") (pinfunction "1_1") (pintype "passive"))
      (node (ref "R7") (pin "2") (pinfunction "2_2") (pintype "passive"))
      (node (ref "U$12") (pin "3") (pinfunction "3_3") (pintype "bidirectional"))
      (node (ref "U$14") (pin "1") (pinfunction "VDD_1") (pintype "bidirectional"))
      (node (ref "U$14") (pin "4") (pinfunction "VDDIO_4") (pintype "bidirectional"))
      (node (ref "U$7") (pin "1") (pinfunction "IO_VDD_1") (pintype "bidirectional"))
      (node (ref "U$7") (pin "5") (pinfunction "VDD_5") (pintype "bidirectional"))
      (node (ref "U$8") (pin "15") (pinfunction "VDD_15") (pintype "bidirectional"))
      (node (ref "U$8") (pin "17") (pinfunction "SPI_CSB_17") (pintype "bidirectional"))
      (node (ref "U$8") (pin "18") (pinfunction "VDDIO_18") (pintype "bidirectional"))
    )
    (net (code "31") (name "GND") (class "Default")
      (node (ref "BATTERY") (pin "1") (pinfunction "1_1") (pintype "passive"))
      (node (ref "C1") (pin "2") (pinfunction "2_2") (pintype "passive"))
      (node (ref "C10") (pin "2") (pinfunction "2_2") (pintype "passive"))
      (node (ref "C11") (pin "2") (pinfunction "2_2") (pintype "passive"))
      (node (ref "C13") (pin "2") (pinfunction "2_2") (pintype "passive"))
      (node (ref "C15") (pin "1") (pinfunction "1_1") (pintype "passive"))
      (node (ref "C2") (pin "2") (pinfunction "2_2") (pintype "passive"))
      (node (ref "C20") (pin "1") (pinfunction "1_1") (pintype "passive"))
      (node (ref "C21") (pin "2") (pinfunction "2_2") (pintype "passive"))
      (node (ref "C23") (pin "1") (pinfunction "1_1") (pintype "passive"))
      (node (ref "C24") (pin "2") (pinfunction "2_2") (pintype "passive"))
      (node (ref "C26") (pin "2") (pinfunction "2_2") (pintype "passive"))
      (node (ref "C27") (pin "1") (pinfunction "1_1") (pintype "passive"))
      (node (ref "C28") (pin "2") (pinfunction "2_2") (pintype "passive"))
      (node (ref "C29") (pin "2") (pinfunction "2_2") (pintype "passive"))
      (node (ref "C3") (pin "2") (pinfunction "2_2") (pintype "passive"))
      (node (ref "C30") (pin "2") (pinfunction "2_2") (pintype "passive"))
      (node (ref "C33") (pin "1") (pinfunction "1_1") (pintype "passive"))
      (node (ref "C34") (pin "2") (pinfunction "2_2") (pintype "passive"))
      (node (ref "C35") (pin "1") (pinfunction "1_1") (pintype "passive"))
      (node (ref "C4") (pin "2") (pinfunction "2_2") (pintype "passive"))
      (node (ref "C5") (pin "2") (pinfunction "2_2") (pintype "passive"))
      (node (ref "C6") (pin "2") (pinfunction "2_2") (pintype "passive"))
      (node (ref "C7") (pin "2") (pinfunction "2_2") (pintype "passive"))
      (node (ref "C8") (pin "2") (pinfunction "2_2") (pintype "passive"))
      (node (ref "C9") (pin "2") (pinfunction "2_2") (pintype "passive"))
      (node (ref "CN1") (pin "2") (pinfunction "1_2") (pintype "passive"))
      (node (ref "D10") (pin "1") (pinfunction "1_1") (pintype "bidirectional"))
      (node (ref "D11") (pin "1") (pinfunction "1_1") (pintype "bidirectional"))
      (node (ref "D5") (pin "1") (pinfunction "1_1") (pintype "bidirectional"))
      (node (ref "D6") (pin "1") (pinfunction "1_1") (pintype "bidirectional"))
      (node (ref "D9") (pin "1") (pinfunction "1_1") (pintype "bidirectional"))
      (node (ref "Q3") (pin "1") (pinfunction "G_1") (pintype "bidirectional"))
      (node (ref "Q7") (pin "2") (pinfunction "S_2") (pintype "bidirectional"))
      (node (ref "R11") (pin "2") (pinfunction "2_2") (pintype "passive"))
      (node (ref "R20") (pin "2") (pinfunction "2_2") (pintype "passive"))
      (node (ref "R21") (pin "2") (pinfunction "2_2") (pintype "passive"))
      (node (ref "R29") (pin "1") (pinfunction "1_1") (pintype "passive"))
      (node (ref "R3") (pin "2") (pinfunction "2_2") (pintype "passive"))
      (node (ref "R43") (pin "1") (pinfunction "1_1") (pintype "passive"))
      (node (ref "R5") (pin "1") (pinfunction "1_1") (pintype "passive"))
      (node (ref "R52") (pin "1") (pinfunction "1_1") (pintype "passive"))
      (node (ref "R53") (pin "1") (pinfunction "1_1") (pintype "passive"))
      (node (ref "R8") (pin "2") (pinfunction "2_2") (pintype "passive"))
      (node (ref "S2") (pin "1") (pinfunction "S_1") (pintype "passive"))
      (node (ref "S2") (pin "2") (pinfunction "S1_2") (pintype "passive"))
      (node (ref "SP1") (pin "P$1") (pinfunction "P$1_P$1") (pintype "bidirectional"))
      (node (ref "SP3") (pin "P$1") (pinfunction "P$1_P$1") (pintype "bidirectional"))
      (node (ref "SP4") (pin "P$1") (pinfunction "P$1_P$1") (pintype "bidirectional"))
      (node (ref "SP5") (pin "P$2") (pinfunction "P$2_P$2") (pintype "bidirectional"))
      (node (ref "SP6") (pin "P$1") (pinfunction "P$1_P$1") (pintype "bidirectional"))
      (node (ref "U$1") (pin "3") (pinfunction "VSS_3") (pintype "bidirectional"))
      (node (ref "U$10") (pin "21") (pinfunction "GPIO_A_21") (pintype "bidirectional"))
      (node (ref "U$10") (pin "22") (pinfunction "VSS_22") (pintype "bidirectional"))
      (node (ref "U$10") (pin "23") (pinfunction "VSS_23") (pintype "bidirectional"))
      (node (ref "U$10") (pin "25") (pinfunction "VSS_25") (pintype "bidirectional"))
      (node (ref "U$10") (pin "28") (pinfunction "GPIO_B_28") (pintype "bidirectional"))
      (node (ref "U$10") (pin "30") (pinfunction "SMBA_30") (pintype "bidirectional"))
      (node (ref "U$10") (pin "6") (pinfunction "VAUX_6") (pintype "bidirectional"))
      (node (ref "U$10") (pin "8") (pinfunction "PRES_8") (pintype "bidirectional"))
      (node (ref "U$10") (pin "9") (pinfunction "KEYIN_9") (pintype "bidirectional"))
      (node (ref "U$13") (pin "2") (pinfunction "VSS_2") (pintype "bidirectional"))
      (node (ref "U$14") (pin "3") (pinfunction "GND_3") (pintype "bidirectional"))
      (node (ref "U$2") (pin "1") (pinfunction "GND1_1") (pintype "bidirectional"))
      (node (ref "U$2") (pin "18") (pinfunction "GND8_18") (pintype "bidirectional"))
      (node (ref "U$2") (pin "2") (pinfunction "GND2_2") (pintype "bidirectional"))
      (node (ref "U$2") (pin "25") (pinfunction "GND9_25") (pintype "bidirectional"))
      (node (ref "U$2") (pin "3") (pinfunction "GND3_3") (pintype "bidirectional"))
      (node (ref "U$2") (pin "36") (pinfunction "GND10_36") (pintype "bidirectional"))
      (node (ref "U$2") (pin "4") (pinfunction "GND4_4") (pintype "bidirectional"))
      (node (ref "U$2") (pin "5") (pinfunction "GND5_5") (pintype "bidirectional"))
      (node (ref "U$2") (pin "6") (pinfunction "GND6_6") (pintype "bidirectional"))
      (node (ref "U$2") (pin "7") (pinfunction "GND7_7") (pintype "bidirectional"))
      (node (ref "U$3") (pin "10") (pinfunction "10A_10") (pintype "bidirectional"))
      (node (ref "U$4") (pin "2") (pinfunction "VSS_2") (pintype "bidirectional"))
      (node (ref "U$6") (pin "5") (pinfunction "GND_5") (pintype "bidirectional"))
      (node (ref "U$7") (pin "4") (pinfunction "GND_4") (pintype "bidirectional"))
      (node (ref "U$7") (pin "6") (pinfunction "RSVD_6") (pintype "bidirectional"))
      (node (ref "U$7") (pin "8") (pinfunction "ADDR_8") (pintype "bidirectional"))
      (node (ref "U$8") (pin "1") (pinfunction "GND_1") (pintype "bidirectional"))
      (node (ref "U$8") (pin "10") (pinfunction "GND_10") (pintype "bidirectional"))
      (node (ref "U$8") (pin "13") (pinfunction "SA0/MISO_13") (pintype "bidirectional"))
      (node (ref "U$8") (pin "14") (pinfunction "GND_14") (pintype "bidirectional"))
      (node (ref "U$8") (pin "19") (pinfunction "GND_19") (pintype "bidirectional"))
      (node (ref "U$8") (pin "20") (pinfunction "GND_20") (pintype "bidirectional"))
      (node (ref "U$8") (pin "21") (pinfunction "GND_21") (pintype "bidirectional"))
      (node (ref "U$8") (pin "22") (pinfunction "GND_22") (pintype "bidirectional"))
      (node (ref "U$8") (pin "23") (pinfunction "GND_23") (pintype "bidirectional"))
      (node (ref "U$8") (pin "24") (pinfunction "GND_24") (pintype "bidirectional"))
      (node (ref "U$8") (pin "5") (pinfunction "GND_5") (pintype "bidirectional"))
      (node (ref "U$8") (pin "6") (pinfunction "GND_6") (pintype "bidirectional"))
      (node (ref "U$8") (pin "7") (pinfunction "GND_7") (pintype "bidirectional"))
      (node (ref "U$8") (pin "8") (pinfunction "I2C_B/SPI_8") (pintype "bidirectional"))
      (node (ref "U$8") (pin "9") (pinfunction "GND_9") (pintype "bidirectional"))
      (node (ref "U$9") (pin "2") (pinfunction "P$2_2") (pintype "bidirectional"))
    )
    (net (code "32") (name "Net-(C31-Pad2)") (class "Default")
      (node (ref "C31") (pin "2") (pinfunction "2_2") (pintype "passive"))
      (node (ref "C32") (pin "1") (pinfunction "1_1") (pintype "passive"))
    )
    (net (code "33") (name "Net-(C36-Pad2)") (class "Default")
      (node (ref "C36") (pin "2") (pinfunction "2_2") (pintype "passive"))
      (node (ref "C37") (pin "1") (pinfunction "1_1") (pintype "passive"))
    )
    (net (code "34") (name "Net-(CN1-2)") (class "Default")
      (node (ref "CN1") (pin "1") (pinfunction "2_1") (pintype "passive"))
      (node (ref "U$5") (pin "2") (pinfunction "2_2") (pintype "bidirectional"))
    )
    (net (code "35") (name "Net-(D1-PadP$2)") (class "Default")
      (node (ref "D1") (pin "P$2") (pinfunction "P$2_P$2") (pintype "bidirectional"))
      (node (ref "R17") (pin "1") (pinfunction "1_1") (pintype "passive"))
      (node (ref "R18") (pin "2") (pinfunction "2_2") (pintype "passive"))
    )
    (net (code "36") (name "Net-(D2-PadP$1)") (class "Default")
      (node (ref "D2") (pin "P$1") (pinfunction "P$1_P$1") (pintype "bidirectional"))
      (node (ref "R24") (pin "1") (pinfunction "1_1") (pintype "passive"))
      (node (ref "R25") (pin "2") (pinfunction "2_2") (pintype "passive"))
    )
    (net (code "37") (name "Net-(D3-2)") (class "Default")
      (node (ref "D3") (pin "P$2") (pinfunction "2_P$2") (pintype "bidirectional"))
      (node (ref "Q4") (pin "1") (pinfunction "G_1") (pintype "bidirectional"))
      (node (ref "R33") (pin "2") (pinfunction "2_2") (pintype "passive"))
      (node (ref "R34") (pin "1") (pinfunction "1_1") (pintype "passive"))
    )
    (net (code "38") (name "Net-(D4-PadP$2)") (class "Default")
      (node (ref "D4") (pin "P$2") (pinfunction "P$2_P$2") (pintype "bidirectional"))
      (node (ref "R34") (pin "2") (pinfunction "2_2") (pintype "passive"))
    )
    (net (code "39") (name "Net-(D5-Pad2)") (class "Default")
      (node (ref "D5") (pin "2") (pinfunction "2_2") (pintype "bidirectional"))
      (node (ref "R48") (pin "2") (pinfunction "2_2") (pintype "passive"))
      (node (ref "R50") (pin "1") (pinfunction "1_1") (pintype "passive"))
      (node (ref "R52") (pin "2") (pinfunction "2_2") (pintype "passive"))
    )
    (net (code "40") (name "Net-(D6-Pad2)") (class "Default")
      (node (ref "D6") (pin "2") (pinfunction "2_2") (pintype "bidirectional"))
      (node (ref "R49") (pin "2") (pinfunction "2_2") (pintype "passive"))
      (node (ref "R51") (pin "1") (pinfunction "1_1") (pintype "passive"))
      (node (ref "R53") (pin "2") (pinfunction "2_2") (pintype "passive"))
    )
    (net (code "41") (name "Net-(D10-Pad2)") (class "Default")
      (node (ref "D10") (pin "2") (pinfunction "2_2") (pintype "bidirectional"))
      (node (ref "R54") (pin "1") (pinfunction "1_1") (pintype "passive"))
      (node (ref "R57") (pin "2") (pinfunction "2_2") (pintype "passive"))
    )
    (net (code "42") (name "Net-(D11-Pad2)") (class "Default")
      (node (ref "D11") (pin "2") (pinfunction "2_2") (pintype "bidirectional"))
      (node (ref "R55") (pin "1") (pinfunction "1_1") (pintype "passive"))
      (node (ref "R56") (pin "2") (pinfunction "2_2") (pintype "passive"))
    )
    (net (code "43") (name "Net-(LED1-PadC)") (class "Default")
      (node (ref "LED1") (pin "C") (pinfunction "C_C") (pintype "passive"))
      (node (ref "R5") (pin "2") (pinfunction "2_2") (pintype "passive"))
    )
    (net (code "44") (name "Net-(LED2-PadA)") (class "Default")
      (node (ref "LED2") (pin "A") (pinfunction "A_A") (pintype "passive"))
      (node (ref "R4") (pin "2") (pinfunction "2_2") (pintype "passive"))
    )
    (net (code "45") (name "Net-(LED3-PadC)") (class "Default")
      (node (ref "LED3") (pin "C") (pinfunction "C_C") (pintype "passive"))
      (node (ref "R8") (pin "1") (pinfunction "1_1") (pintype "passive"))
    )
    (net (code "46") (name "Net-(LED4-PadA)") (class "Default")
      (node (ref "LED4") (pin "A") (pinfunction "A_A") (pintype "passive"))
      (node (ref "R40") (pin "1") (pinfunction "1_1") (pintype "passive"))
    )
    (net (code "47") (name "Net-(LED5-PadA)") (class "Default")
      (node (ref "LED5") (pin "A") (pinfunction "A_A") (pintype "passive"))
      (node (ref "R41") (pin "1") (pinfunction "1_1") (pintype "passive"))
    )
    (net (code "48") (name "Net-(LED6-PadA)") (class "Default")
      (node (ref "LED6") (pin "A") (pinfunction "A_A") (pintype "passive"))
      (node (ref "R39") (pin "1") (pinfunction "1_1") (pintype "passive"))
    )
    (net (code "49") (name "Net-(LED7-PadA)") (class "Default")
      (node (ref "LED7") (pin "A") (pinfunction "A_A") (pintype "passive"))
      (node (ref "R38") (pin "1") (pinfunction "1_1") (pintype "passive"))
    )
    (net (code "50") (name "Net-(LED8-PadA)") (class "Default")
      (node (ref "LED8") (pin "A") (pinfunction "A_A") (pintype "passive"))
      (node (ref "R37") (pin "1") (pinfunction "1_1") (pintype "passive"))
    )
    (net (code "51") (name "Net-(Q1-D-Pad1A)") (class "Default")
      (node (ref "Q1") (pin "1A") (pinfunction "D_1A") (pintype "bidirectional"))
      (node (ref "Q1") (pin "1B") (pinfunction "D_1B") (pintype "bidirectional"))
      (node (ref "Q1") (pin "1C") (pinfunction "D_1C") (pintype "bidirectional"))
      (node (ref "Q1") (pin "1D") (pinfunction "D_1D") (pintype "bidirectional"))
      (node (ref "Q1") (pin "1E") (pinfunction "D_1E") (pintype "bidirectional"))
      (node (ref "Q2") (pin "1A") (pinfunction "D_1A") (pintype "bidirectional"))
      (node (ref "Q2") (pin "1B") (pinfunction "D_1B") (pintype "bidirectional"))
      (node (ref "Q2") (pin "1C") (pinfunction "D_1C") (pintype "bidirectional"))
      (node (ref "Q2") (pin "1D") (pinfunction "D_1D") (pintype "bidirectional"))
      (node (ref "Q2") (pin "1E") (pinfunction "D_1E") (pintype "bidirectional"))
      (node (ref "R32") (pin "1") (pinfunction "1_1") (pintype "passive"))
    )
    (net (code "52") (name "Net-(Q2-G)") (class "Default")
      (node (ref "D2") (pin "P$2") (pinfunction "P$2_P$2") (pintype "bidirectional"))
      (node (ref "Q2") (pin "3A") (pinfunction "G_3A") (pintype "bidirectional"))
      (node (ref "R23") (pin "1") (pinfunction "1_1") (pintype "passive"))
      (node (ref "R24") (pin "2") (pinfunction "2_2") (pintype "passive"))
    )
    (net (code "53") (name "Net-(Q3-D)") (class "Default")
      (node (ref "Q3") (pin "3") (pinfunction "D_3") (pintype "bidirectional"))
      (node (ref "R25") (pin "1") (pinfunction "1_1") (pintype "passive"))
    )
    (net (code "54") (name "Net-(Q4-D)") (class "Default")
      (node (ref "Q4") (pin "3") (pinfunction "D_3") (pintype "bidirectional"))
      (node (ref "R32") (pin "2") (pinfunction "2_2") (pintype "passive"))
    )
    (net (code "55") (name "Net-(Q5-B)") (class "Default")
      (node (ref "Q5") (pin "1") (pinfunction "B_1") (pintype "bidirectional"))
      (node (ref "R35") (pin "1") (pinfunction "1_1") (pintype "passive"))
    )
    (net (code "56") (name "Net-(Q5-C)") (class "Default")
      (node (ref "D4") (pin "P$1") (pinfunction "P$1_P$1") (pintype "bidirectional"))
      (node (ref "Q5") (pin "3") (pinfunction "C_3") (pintype "bidirectional"))
    )
    (net (code "57") (name "Net-(Q6-D)") (class "Default")
      (node (ref "Q6") (pin "3") (pinfunction "D_3") (pintype "bidirectional"))
      (node (ref "R42") (pin "2") (pinfunction "2_2") (pintype "passive"))
    )
    (net (code "58") (name "Net-(Q6-G)") (class "Default")
      (node (ref "Q6") (pin "1") (pinfunction "G_1") (pintype "bidirectional"))
      (node (ref "R45") (pin "1") (pinfunction "1_1") (pintype "passive"))
      (node (ref "R46") (pin "2") (pinfunction "2_2") (pintype "passive"))
    )
    (net (code "59") (name "Net-(Q7-D)") (class "Default")
      (node (ref "Q7") (pin "3") (pinfunction "D_3") (pintype "bidirectional"))
      (node (ref "R46") (pin "1") (pinfunction "1_1") (pintype "passive"))
    )
    (net (code "60") (name "Net-(Q7-G)") (class "Default")
      (node (ref "Q7") (pin "1") (pinfunction "G_1") (pintype "bidirectional"))
      (node (ref "R44") (pin "2") (pinfunction "2_2") (pintype "passive"))
      (node (ref "U$10") (pin "12") (pinfunction "VEN_12") (pintype "bidirectional"))
    )
    (net (code "61") (name "Net-(S1-P)") (class "Default")
      (node (ref "R30") (pin "2") (pinfunction "2_2") (pintype "passive"))
      (node (ref "S1") (pin "3") (pinfunction "P_3") (pintype "passive"))
      (node (ref "S1") (pin "4") (pinfunction "P1_4") (pintype "passive"))
    )
    (net (code "62") (name "Net-(S1-S)") (class "Default")
      (node (ref "C29") (pin "1") (pinfunction "1_1") (pintype "passive"))
      (node (ref "R29") (pin "2") (pinfunction "2_2") (pintype "passive"))
      (node (ref "S1") (pin "1") (pinfunction "S_1") (pintype "passive"))
      (node (ref "S1") (pin "2") (pinfunction "S1_2") (pintype "passive"))
      (node (ref "U$1") (pin "6") (pinfunction "TS1_6") (pintype "bidirectional"))
    )
    (net (code "63") (name "Net-(S2-P)") (class "Default")
      (node (ref "R47") (pin "1") (pinfunction "1_1") (pintype "passive"))
      (node (ref "S2") (pin "3") (pinfunction "P_3") (pintype "passive"))
      (node (ref "S2") (pin "4") (pinfunction "P1_4") (pintype "passive"))
      (node (ref "U$10") (pin "14") (pinfunction "DISP_14") (pintype "bidirectional"))
    )
    (net (code "64") (name "Net-(U$1-BAT)") (class "Default")
      (node (ref "C21") (pin "1") (pinfunction "1_1") (pintype "passive"))
      (node (ref "R18") (pin "1") (pinfunction "1_1") (pintype "passive"))
      (node (ref "U$1") (pin "10") (pinfunction "BAT_10") (pintype "bidirectional"))
      (node (ref "U$1") (pin "9") (pinfunction "REGSRC_9") (pintype "bidirectional"))
    )
    (net (code "65") (name "Net-(U$1-CAP1)") (class "Default")
      (node (ref "C27") (pin "2") (pinfunction "2_2") (pintype "passive"))
      (node (ref "U$1") (pin "7") (pinfunction "CAP1_7") (pintype "bidirectional"))
    )
    (net (code "66") (name "Net-(U$1-SRN)") (class "Default")
      (node (ref "C22") (pin "1") (pinfunction "1_1") (pintype "passive"))
      (node (ref "C23") (pin "2") (pinfunction "2_2") (pintype "passive"))
      (node (ref "R19") (pin "1") (pinfunction "1_1") (pintype "passive"))
      (node (ref "U$1") (pin "19") (pinfunction "SRN_19") (pintype "bidirectional"))
    )
    (net (code "67") (name "Net-(U$1-SRP)") (class "Default")
      (node (ref "C22") (pin "2") (pinfunction "2_2") (pintype "passive"))
      (node (ref "C24") (pin "1") (pinfunction "1_1") (pintype "passive"))
      (node (ref "R20") (pin "1") (pinfunction "1_1") (pintype "passive"))
      (node (ref "U$1") (pin "18") (pinfunction "SRP_18") (pintype "bidirectional"))
    )
    (net (code "68") (name "Net-(U$2-AVDD)") (class "Default")
      (node (ref "R6") (pin "1") (pinfunction "1_1") (pintype "passive"))
      (node (ref "U$2") (pin "17") (pinfunction "DVDD_17") (pintype "bidirectional"))
      (node (ref "U$2") (pin "8") (pinfunction "AVDD_8") (pintype "bidirectional"))
    )
    (net (code "69") (name "Net-(U$2-P1_0)") (class "Default")
      (node (ref "LED1") (pin "A") (pinfunction "A_A") (pintype "passive"))
      (node (ref "U$2") (pin "24") (pinfunction "P1_0_24") (pintype "bidirectional"))
    )
    (net (code "70") (name "Net-(U$2-RESET#)") (class "Default")
      (node (ref "U$2") (pin "34") (pinfunction "RESET#_34") (pintype "bidirectional"))
      (node (ref "U$3") (pin "4") (pinfunction "4A_4") (pintype "bidirectional"))
    )
    (net (code "71") (name "Net-(U$4-BYPASS)") (class "Default")
      (node (ref "C2") (pin "1") (pinfunction "1_1") (pintype "passive"))
      (node (ref "U$4") (pin "4") (pinfunction "BYPASS_4") (pintype "bidirectional"))
    )
    (net (code "72") (name "Net-(U$8-RST_B)") (class "Default")
      (node (ref "R7") (pin "1") (pinfunction "1_1") (pintype "passive"))
      (node (ref "U$8") (pin "4") (pinfunction "RST_B_4") (pintype "bidirectional"))
    )
    (net (code "73") (name "Net-(U$8-VREGD)") (class "Default")
      (node (ref "C6") (pin "1") (pinfunction "1_1") (pintype "passive"))
      (node (ref "U$8") (pin "16") (pinfunction "VREGD_16") (pintype "bidirectional"))
    )
    (net (code "74") (name "Net-(U$9-P$1)") (class "Default")
      (node (ref "C31") (pin "1") (pinfunction "1_1") (pintype "passive"))
      (node (ref "Q1") (pin "2A") (pinfunction "S_2A") (pintype "bidirectional"))
      (node (ref "Q1") (pin "2B") (pinfunction "S_2B") (pintype "bidirectional"))
      (node (ref "Q1") (pin "2C") (pinfunction "S_2C") (pintype "bidirectional"))
      (node (ref "R19") (pin "2") (pinfunction "2_2") (pintype "passive"))
      (node (ref "R22") (pin "2") (pinfunction "2_2") (pintype "passive"))
      (node (ref "U$9") (pin "1") (pinfunction "P$1_1") (pintype "bidirectional"))
    )
    (net (code "75") (name "Net-(U$10-BAT)") (class "Default")
      (node (ref "C34") (pin "1") (pinfunction "1_1") (pintype "passive"))
      (node (ref "R42") (pin "1") (pinfunction "1_1") (pintype "passive"))
      (node (ref "R43") (pin "2") (pinfunction "2_2") (pintype "passive"))
      (node (ref "U$10") (pin "7") (pinfunction "BAT_7") (pintype "bidirectional"))
    )
    (net (code "76") (name "Net-(U$10-LED1)") (class "Default")
      (node (ref "LED4") (pin "C") (pinfunction "C_C") (pintype "passive"))
      (node (ref "U$10") (pin "16") (pinfunction "LED1_16") (pintype "bidirectional"))
    )
    (net (code "77") (name "Net-(U$10-LED2)") (class "Default")
      (node (ref "LED5") (pin "C") (pinfunction "C_C") (pintype "passive"))
      (node (ref "U$10") (pin "17") (pinfunction "LED2_17") (pintype "bidirectional"))
    )
    (net (code "78") (name "Net-(U$10-LED3)") (class "Default")
      (node (ref "LED6") (pin "C") (pinfunction "C_C") (pintype "passive"))
      (node (ref "U$10") (pin "18") (pinfunction "LED3_18") (pintype "bidirectional"))
    )
    (net (code "79") (name "Net-(U$10-LED4)") (class "Default")
      (node (ref "LED7") (pin "C") (pinfunction "C_C") (pintype "passive"))
      (node (ref "U$10") (pin "19") (pinfunction "LED4_19") (pintype "bidirectional"))
    )
    (net (code "80") (name "Net-(U$10-LED5)") (class "Default")
      (node (ref "LED8") (pin "C") (pinfunction "C_C") (pintype "passive"))
      (node (ref "U$10") (pin "20") (pinfunction "LED5_20") (pintype "bidirectional"))
    )
    (net (code "81") (name "Net-(U$10-MRST)") (class "Default")
      (node (ref "R36") (pin "1") (pinfunction "1_1") (pintype "passive"))
      (node (ref "U$10") (pin "24") (pinfunction "MRST_24") (pintype "bidirectional"))
    )
    (net (code "82") (name "Net-(U$10-PRECHG)") (class "Default")
      (node (ref "R35") (pin "2") (pinfunction "2_2") (pintype "passive"))
      (node (ref "U$10") (pin "5") (pinfunction "PRECHG_5") (pintype "bidirectional"))
    )
    (net (code "83") (name "Net-(U$10-RBI)") (class "Default")
      (node (ref "C33") (pin "2") (pinfunction "2_2") (pintype "passive"))
      (node (ref "U$10") (pin "27") (pinfunction "RBI_27") (pintype "bidirectional"))
    )
    (net (code "84") (name "Net-(U$10-SMBC)") (class "Default")
      (node (ref "R48") (pin "1") (pinfunction "1_1") (pintype "passive"))
      (node (ref "U$10") (pin "13") (pinfunction "SMBC_13") (pintype "bidirectional"))
    )
    (net (code "85") (name "Net-(U$10-SMBD)") (class "Default")
      (node (ref "R49") (pin "1") (pinfunction "1_1") (pintype "passive"))
      (node (ref "U$10") (pin "11") (pinfunction "SMBD_11") (pintype "bidirectional"))
    )
    (net (code "86") (name "Net-(U$13-PROG)") (class "Default")
      (node (ref "R3") (pin "1") (pinfunction "1_1") (pintype "passive"))
      (node (ref "U$13") (pin "5") (pinfunction "PROG_5") (pintype "bidirectional"))
    )
    (net (code "87") (name "Net-(U$13-STAT)") (class "Default")
      (node (ref "LED2") (pin "C") (pinfunction "C_C") (pintype "passive"))
      (node (ref "U$13") (pin "1") (pinfunction "STAT_1") (pintype "bidirectional"))
    )
    (net (code "88") (name "Net-(U$13-VBAT)") (class "Default")
      (node (ref "U$13") (pin "3") (pinfunction "VBAT_3") (pintype "bidirectional"))
      (node (ref "U$5") (pin "1") (pinfunction "1_1") (pintype "bidirectional"))
    )
    (net (code "89") (name "Net-(U$13-VDD)") (class "Default")
      (node (ref "R4") (pin "1") (pinfunction "1_1") (pintype "passive"))
      (node (ref "U$13") (pin "4") (pinfunction "VDD_4") (pintype "bidirectional"))
      (node (ref "U$6") (pin "1") (pinfunction "VBUS_1") (pintype "bidirectional"))
    )
    (net (code "90") (name "Net-(U$14-CAP)") (class "Default")
      (node (ref "C13") (pin "1") (pinfunction "1_1") (pintype "passive"))
      (node (ref "U$14") (pin "2") (pinfunction "CAP_2") (pintype "bidirectional"))
    )
    (net (code "91") (name "unconnected-(U$2-NC-Pad16)") (class "Default")
      (node (ref "U$2") (pin "16") (pinfunction "NC_16") (pintype "bidirectional"))
    )
    (net (code "92") (name "unconnected-(U$2-NC2-Pad35)") (class "Default")
      (node (ref "U$2") (pin "35") (pinfunction "NC2_35") (pintype "bidirectional"))
    )
    (net (code "93") (name "unconnected-(U$2-P0_0-Pad33)") (class "Default")
      (node (ref "U$2") (pin "33") (pinfunction "P0_0_33") (pintype "bidirectional"))
    )
    (net (code "94") (name "unconnected-(U$2-P0_1-Pad32)") (class "Default")
      (node (ref "U$2") (pin "32") (pinfunction "P0_1_32") (pintype "bidirectional"))
    )
    (net (code "95") (name "unconnected-(U$2-P0_2-Pad31)") (class "Default")
      (node (ref "U$2") (pin "31") (pinfunction "P0_2_31") (pintype "bidirectional"))
    )
    (net (code "96") (name "unconnected-(U$2-P0_3-Pad30)") (class "Default")
      (node (ref "U$2") (pin "30") (pinfunction "P0_3_30") (pintype "bidirectional"))
    )
    (net (code "97") (name "unconnected-(U$2-P0_4-Pad29)") (class "Default")
      (node (ref "U$2") (pin "29") (pinfunction "P0_4_29") (pintype "bidirectional"))
    )
    (net (code "98") (name "unconnected-(U$2-P0_5-Pad28)") (class "Default")
      (node (ref "U$2") (pin "28") (pinfunction "P0_5_28") (pintype "bidirectional"))
    )
    (net (code "99") (name "unconnected-(U$2-P0_6-Pad27)") (class "Default")
      (node (ref "U$2") (pin "27") (pinfunction "P0_6_27") (pintype "bidirectional"))
    )
    (net (code "100") (name "unconnected-(U$2-P0_7-Pad26)") (class "Default")
      (node (ref "U$2") (pin "26") (pinfunction "P0_7_26") (pintype "bidirectional"))
    )
    (net (code "101") (name "unconnected-(U$2-P1_1-Pad23)") (class "Default")
      (node (ref "U$2") (pin "23") (pinfunction "P1_1_23") (pintype "bidirectional"))
    )
    (net (code "102") (name "unconnected-(U$2-P1_2-Pad22)") (class "Default")
      (node (ref "U$2") (pin "22") (pinfunction "P1_2_22") (pintype "bidirectional"))
    )
    (net (code "103") (name "unconnected-(U$2-P1_3-Pad21)") (class "Default")
      (node (ref "U$2") (pin "21") (pinfunction "P1_3_21") (pintype "bidirectional"))
    )
    (net (code "104") (name "unconnected-(U$2-P1_4-Pad20)") (class "Default")
      (node (ref "U$2") (pin "20") (pinfunction "P1_4_20") (pintype "bidirectional"))
    )
    (net (code "105") (name "unconnected-(U$2-P1_5-Pad19)") (class "Default")
      (node (ref "U$2") (pin "19") (pinfunction "P1_5_19") (pintype "bidirectional"))
    )
    (net (code "106") (name "unconnected-(U$2-P1_6-Pad13)") (class "Default")
      (node (ref "U$2") (pin "13") (pinfunction "P1_6_13") (pintype "bidirectional"))
    )
    (net (code "107") (name "unconnected-(U$2-P1_7-Pad12)") (class "Default")
      (node (ref "U$2") (pin "12") (pinfunction "P1_7_12") (pintype "bidirectional"))
    )
    (net (code "108") (name "unconnected-(U$2-P2_0-Pad11)") (class "Default")
      (node (ref "U$2") (pin "11") (pinfunction "P2_0_11") (pintype "bidirectional"))
    )
    (net (code "109") (name "unconnected-(U$3-1A-Pad1)") (class "Default")
      (node (ref "U$3") (pin "1") (pinfunction "1A_1") (pintype "bidirectional"))
    )
    (net (code "110") (name "unconnected-(U$3-2A-Pad2)") (class "Default")
      (node (ref "U$3") (pin "2") (pinfunction "2A_2") (pintype "bidirectional"))
    )
    (net (code "111") (name "unconnected-(U$3-3A-Pad3)") (class "Default")
      (node (ref "U$3") (pin "3") (pinfunction "3A_3") (pintype "bidirectional"))
    )
    (net (code "112") (name "unconnected-(U$3-5A-Pad5)") (class "Default")
      (node (ref "U$3") (pin "5") (pinfunction "5A_5") (pintype "bidirectional"))
    )
    (net (code "113") (name "unconnected-(U$3-6A-Pad6)") (class "Default")
      (node (ref "U$3") (pin "6") (pinfunction "6A_6") (pintype "bidirectional"))
    )
    (net (code "114") (name "unconnected-(U$6-D+-Pad2)") (class "Default")
      (node (ref "U$6") (pin "2") (pinfunction "D+_2") (pintype "bidirectional"))
    )
    (net (code "115") (name "unconnected-(U$6-D--Pad3)") (class "Default")
      (node (ref "U$6") (pin "3") (pinfunction "D-_3") (pintype "bidirectional"))
    )
    (net (code "116") (name "unconnected-(U$6-ID-Pad4)") (class "Default")
      (node (ref "U$6") (pin "4") (pinfunction "ID_4") (pintype "bidirectional"))
    )
    (net (code "117") (name "unconnected-(U$7-INT-Pad7)") (class "Default")
      (node (ref "U$7") (pin "7") (pinfunction "INT_7") (pintype "bidirectional"))
    )
    (net (code "118") (name "unconnected-(U$8-INT1-Pad3)") (class "Default")
      (node (ref "U$8") (pin "3") (pinfunction "INT1_3") (pintype "bidirectional"))
    )
    (net (code "119") (name "unconnected-(U$8-INT2{slash}PWR_CTRL-Pad2)") (class "Default")
      (node (ref "U$8") (pin "2") (pinfunction "INT2/PWR_CTRL_2") (pintype "bidirectional"))
    )
    (net (code "120") (name "unconnected-(U$10-ADREN-Pad29)") (class "Default")
      (node (ref "U$10") (pin "29") (pinfunction "ADREN_29") (pintype "bidirectional"))
    )
    (net (code "121") (name "unconnected-(U$10-COM-Pad1)") (class "Default")
      (node (ref "U$10") (pin "1") (pinfunction "COM_1") (pintype "bidirectional"))
    )
    (net (code "122") (name "unconnected-(U$10-PWRM-Pad15)") (class "Default")
      (node (ref "U$10") (pin "15") (pinfunction "PWRM_15") (pintype "bidirectional"))
    )
    (net (code "123") (name "unconnected-(U$10-SAFE-Pad10)") (class "Default")
      (node (ref "U$10") (pin "10") (pinfunction "SAFE_10") (pintype "bidirectional"))
    )
    (net (code "124") (name "unconnected-(U$12-Pad1)") (class "Default")
      (node (ref "U$12") (pin "1") (pinfunction "1_1") (pintype "bidirectional"))
    )
    (net (code "125") (name "unconnected-(U$14-INT1-Pad6)") (class "Default")
      (node (ref "U$14") (pin "6") (pinfunction "INT1_6") (pintype "bidirectional"))
    )
    (net (code "126") (name "unconnected-(U$14-INT2-Pad5)") (class "Default")
      (node (ref "U$14") (pin "5") (pinfunction "INT2_5") (pintype "bidirectional"))
    )
  )
)
